# alphanewt_v0_5.net
KiCad netlist of a schematic drawn in EAGLE
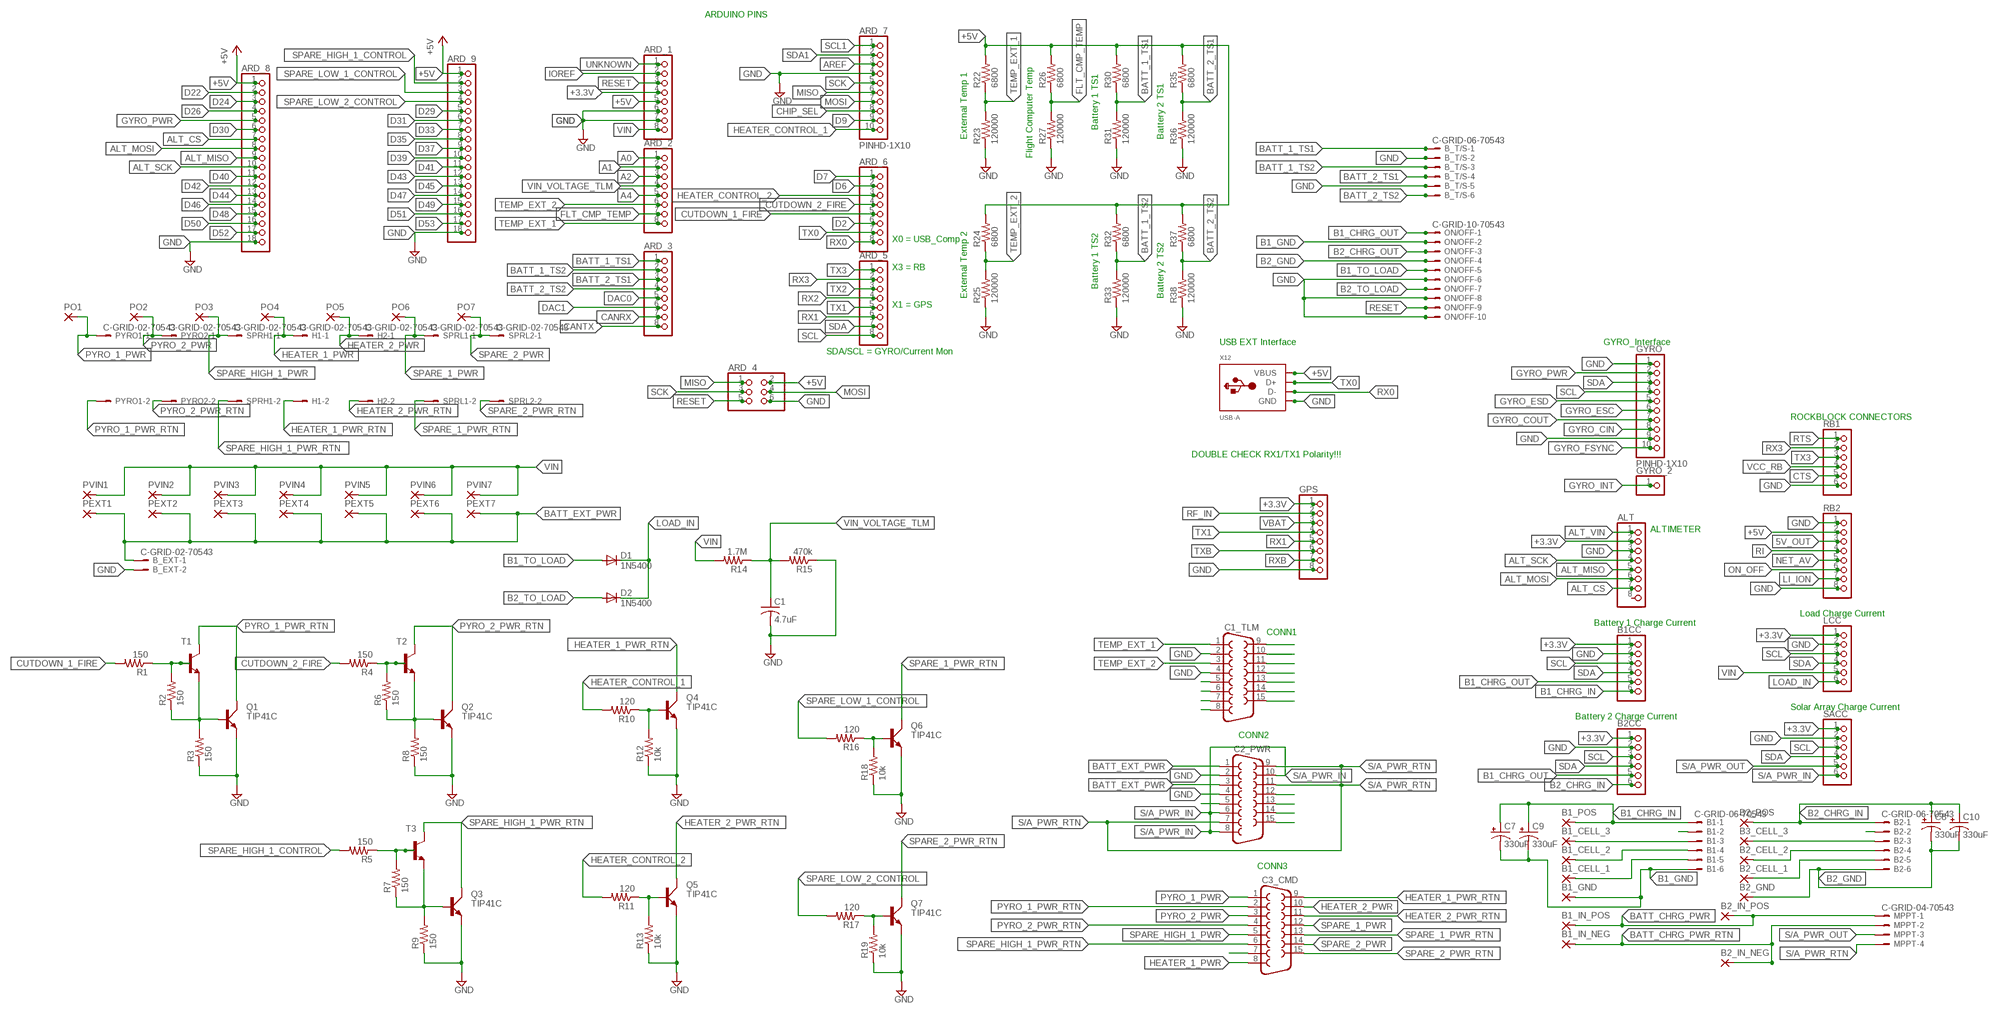
[diagram p0: schematic, sheet 1]

(export (version "E")
  (design (tool "Eeschema 10.0.6"))
  (components
    (comp (ref "ALT")
      (value "PINHD-1X8BIG")
      (footprint "eagle-import:1X08-BIG")
      (libsource (lib "eagle-import") (part "PINHD-1X8BIG"))
    )
    (comp (ref "ARD_1")
      (value "PINHD-1X8BIG")
      (footprint "eagle-import:1X08-BIG")
      (libsource (lib "eagle-import") (part "PINHD-1X8BIG"))
    )
    (comp (ref "ARD_2")
      (value "PINHD-1X8BIG")
      (footprint "eagle-import:1X08-BIG")
      (libsource (lib "eagle-import") (part "PINHD-1X8BIG"))
    )
    (comp (ref "ARD_3")
      (value "PINHD-1X8BIG")
      (footprint "eagle-import:1X08-BIG")
      (libsource (lib "eagle-import") (part "PINHD-1X8BIG"))
    )
    (comp (ref "ARD_4")
      (value "PINHD-2X3")
      (footprint "eagle-import:2X03")
      (libsource (lib "eagle-import") (part "PINHD-2X3"))
    )
    (comp (ref "ARD_5")
      (value "PINHD-1X8BIG")
      (footprint "eagle-import:1X08-BIG")
      (libsource (lib "eagle-import") (part "PINHD-1X8BIG"))
    )
    (comp (ref "ARD_6")
      (value "PINHD-1X8BIG")
      (footprint "eagle-import:1X08-BIG")
      (libsource (lib "eagle-import") (part "PINHD-1X8BIG"))
    )
    (comp (ref "ARD_7")
      (value "PINHD-1X10")
      (footprint "eagle-import:1X10-BIG")
      (libsource (lib "eagle-import") (part "PINHD-1X10"))
    )
    (comp (ref "ARD_8")
      (value "PINHD-1X18-BIG")
      (footprint "eagle-import:1X18-BIG")
      (libsource (lib "eagle-import") (part "PINHD-1X18-BIG"))
    )
    (comp (ref "ARD_9")
      (value "PINHD-1X18-BIG")
      (footprint "eagle-import:1X18-BIG")
      (libsource (lib "eagle-import") (part "PINHD-1X18-BIG"))
    )
    (comp (ref "B1")
      (value "C-GRID-06-70543")
      (footprint "eagle-import:70543-06")
      (fields
        (field (name "MF") "MOLEX")
        (field (name "MPN") "70543-0005")
        (field (name "OC_NEWARK") "59H2647")
      )
      (libsource (lib "eagle-import") (part "C-GRID-06-70543"))
    )
    (comp (ref "B1CC")
      (value "PINHD-1X6B")
      (footprint "eagle-import:1X06-BIG")
      (libsource (lib "eagle-import") (part "PINHD-1X6B"))
    )
    (comp (ref "B1_CELL_1")
      (value "SMD5")
      (footprint "eagle-import:SMD2,54-5,08")
      (libsource (lib "eagle-import") (part "SMD5"))
    )
    (comp (ref "B1_CELL_2")
      (value "SMD5")
      (footprint "eagle-import:SMD2,54-5,08")
      (libsource (lib "eagle-import") (part "SMD5"))
    )
    (comp (ref "B1_CELL_3")
      (value "SMD5")
      (footprint "eagle-import:SMD2,54-5,08")
      (libsource (lib "eagle-import") (part "SMD5"))
    )
    (comp (ref "B1_GND")
      (value "SMD5")
      (footprint "eagle-import:SMD2,54-5,08")
      (libsource (lib "eagle-import") (part "SMD5"))
    )
    (comp (ref "B1_IN_NEG")
      (value "SMD5")
      (footprint "eagle-import:SMD2,54-5,08")
      (libsource (lib "eagle-import") (part "SMD5"))
    )
    (comp (ref "B1_IN_POS")
      (value "SMD5")
      (footprint "eagle-import:SMD2,54-5,08")
      (libsource (lib "eagle-import") (part "SMD5"))
    )
    (comp (ref "B1_POS")
      (value "SMD5")
      (footprint "eagle-import:SMD2,54-5,08")
      (libsource (lib "eagle-import") (part "SMD5"))
    )
    (comp (ref "B2")
      (value "C-GRID-06-70543")
      (footprint "eagle-import:70543-06")
      (fields
        (field (name "MF") "MOLEX")
        (field (name "MPN") "70543-0005")
        (field (name "OC_NEWARK") "59H2647")
      )
      (libsource (lib "eagle-import") (part "C-GRID-06-70543"))
    )
    (comp (ref "B2CC")
      (value "PINHD-1X6B")
      (footprint "eagle-import:1X06-BIG")
      (libsource (lib "eagle-import") (part "PINHD-1X6B"))
    )
    (comp (ref "B2_CELL_1")
      (value "SMD5")
      (footprint "eagle-import:SMD2,54-5,08")
      (libsource (lib "eagle-import") (part "SMD5"))
    )
    (comp (ref "B2_CELL_2")
      (value "SMD5")
      (footprint "eagle-import:SMD2,54-5,08")
      (libsource (lib "eagle-import") (part "SMD5"))
    )
    (comp (ref "B2_GND")
      (value "SMD5")
      (footprint "eagle-import:SMD2,54-5,08")
      (libsource (lib "eagle-import") (part "SMD5"))
    )
    (comp (ref "B2_IN_NEG")
      (value "SMD5")
      (footprint "eagle-import:SMD2,54-5,08")
      (libsource (lib "eagle-import") (part "SMD5"))
    )
    (comp (ref "B2_IN_POS")
      (value "SMD5")
      (footprint "eagle-import:SMD2,54-5,08")
      (libsource (lib "eagle-import") (part "SMD5"))
    )
    (comp (ref "B2_POS")
      (value "SMD5")
      (footprint "eagle-import:SMD2,54-5,08")
      (libsource (lib "eagle-import") (part "SMD5"))
    )
    (comp (ref "B3_CELL_3")
      (value "SMD5")
      (footprint "eagle-import:SMD2,54-5,08")
      (libsource (lib "eagle-import") (part "SMD5"))
    )
    (comp (ref "B_EXT")
      (value "C-GRID-02-70543")
      (footprint "eagle-import:70543-02")
      (fields
        (field (name "MF") "MOLEX")
        (field (name "MPN") "70543-0001")
        (field (name "OC_NEWARK") "59H2645")
      )
      (libsource (lib "eagle-import") (part "C-GRID-02-70543"))
    )
    (comp (ref "B_T/S")
      (value "C-GRID-06-70543")
      (footprint "eagle-import:70543-06")
      (fields
        (field (name "MF") "MOLEX")
        (field (name "MPN") "70543-0005")
        (field (name "OC_NEWARK") "59H2647")
      )
      (libsource (lib "eagle-import") (part "C-GRID-06-70543"))
    )
    (comp (ref "C1")
      (value "4.7uF")
      (footprint "eagle-import:C0805K")
      (fields (field (name "MPN") "C2012X6S1H475K125AC"))
      (libsource (lib "eagle-import") (part "C-USC0805K"))
    )
    (comp (ref "C1_TLM")
      (value "F15HP")
      (footprint "eagle-import:F15HP")
      (fields (field (name "MPN") "5504F1-15S-02A-03"))
      (libsource (lib "eagle-import") (part "F15HP"))
    )
    (comp (ref "C2_PWR")
      (value "F15HP")
      (footprint "eagle-import:F15HP")
      (fields (field (name "MPN") "5504F1-15S-02A-03"))
      (libsource (lib "eagle-import") (part "F15HP"))
    )
    (comp (ref "C3_CMD")
      (value "F15HP")
      (footprint "eagle-import:F15HP")
      (fields (field (name "MPN") "5504F1-15S-02A-03"))
      (libsource (lib "eagle-import") (part "F15HP"))
    )
    (comp (ref "C7")
      (value "330uF")
      (footprint "eagle-import:CT7343")
      (fields (field (name "MPN") "TCN4337M020R0100"))
      (libsource (lib "eagle-import") (part "CPOL-USCT7343"))
    )
    (comp (ref "C8")
      (value "330uF")
      (footprint "eagle-import:CT7343")
      (fields (field (name "MPN") "TCN4337M020R0100"))
      (libsource (lib "eagle-import") (part "CPOL-USCT7343"))
    )
    (comp (ref "C9")
      (value "330uF")
      (footprint "eagle-import:CT7343")
      (fields (field (name "MPN") "TCN4337M020R0100"))
      (libsource (lib "eagle-import") (part "CPOL-USCT7343"))
    )
    (comp (ref "C10")
      (value "330uF")
      (footprint "eagle-import:CT7343")
      (fields (field (name "MPN") "TCN4337M020R0100"))
      (libsource (lib "eagle-import") (part "CPOL-USCT7343"))
    )
    (comp (ref "D1")
      (value "1N5400")
      (footprint "eagle-import:DO201-15")
      (fields (field (name "MPN") "1N5400-E3/54"))
      (libsource (lib "eagle-import") (part "1N5400"))
    )
    (comp (ref "D2")
      (value "1N5400")
      (footprint "eagle-import:DO201-15")
      (fields (field (name "MPN") "1N5400-E3/54"))
      (libsource (lib "eagle-import") (part "1N5400"))
    )
    (comp (ref "GPS")
      (value "PINHD-1X8BIG")
      (footprint "eagle-import:1X08-BIG")
      (libsource (lib "eagle-import") (part "PINHD-1X8BIG"))
    )
    (comp (ref "GYRO")
      (value "PINHD-1X10")
      (footprint "eagle-import:1X10-BIG")
      (libsource (lib "eagle-import") (part "PINHD-1X10"))
    )
    (comp (ref "GYRO_2")
      (value "PINHD-1X1")
      (footprint "eagle-import:1X01")
      (libsource (lib "eagle-import") (part "PINHD-1X1"))
    )
    (comp (ref "H1")
      (value "C-GRID-02-70543")
      (footprint "eagle-import:70543-02")
      (fields
        (field (name "MF") "MOLEX")
        (field (name "MPN") "70543-0001")
        (field (name "OC_NEWARK") "59H2645")
      )
      (libsource (lib "eagle-import") (part "C-GRID-02-70543"))
    )
    (comp (ref "H2")
      (value "C-GRID-02-70543")
      (footprint "eagle-import:70543-02")
      (fields
        (field (name "MF") "MOLEX")
        (field (name "MPN") "70543-0001")
        (field (name "OC_NEWARK") "59H2645")
      )
      (libsource (lib "eagle-import") (part "C-GRID-02-70543"))
    )
    (comp (ref "LCC")
      (value "PINHD-1X6B")
      (footprint "eagle-import:1X06-BIG")
      (libsource (lib "eagle-import") (part "PINHD-1X6B"))
    )
    (comp (ref "MPPT")
      (value "C-GRID-04-70543")
      (footprint "eagle-import:70543-04")
      (fields
        (field (name "MF") "MOLEX")
        (field (name "MPN") "70543-0038")
        (field (name "OC_NEWARK") "59H2665")
      )
      (libsource (lib "eagle-import") (part "C-GRID-04-70543"))
    )
    (comp (ref "ON/OFF")
      (value "C-GRID-10-70543")
      (footprint "eagle-import:70543-10")
      (fields
        (field (name "MF") "MOLEX")
        (field (name "MPN") "70543-0009")
        (field (name "OC_NEWARK") "59H2651")
      )
      (libsource (lib "eagle-import") (part "C-GRID-10-70543"))
    )
    (comp (ref "PEXT1")
      (value "SMD2")
      (footprint "eagle-import:SMD1,27-2,54")
      (libsource (lib "eagle-import") (part "SMD2"))
    )
    (comp (ref "PEXT2")
      (value "SMD2")
      (footprint "eagle-import:SMD1,27-2,54")
      (libsource (lib "eagle-import") (part "SMD2"))
    )
    (comp (ref "PEXT3")
      (value "SMD2")
      (footprint "eagle-import:SMD1,27-2,54")
      (libsource (lib "eagle-import") (part "SMD2"))
    )
    (comp (ref "PEXT4")
      (value "SMD2")
      (footprint "eagle-import:SMD1,27-2,54")
      (libsource (lib "eagle-import") (part "SMD2"))
    )
    (comp (ref "PEXT5")
      (value "SMD2")
      (footprint "eagle-import:SMD1,27-2,54")
      (libsource (lib "eagle-import") (part "SMD2"))
    )
    (comp (ref "PEXT6")
      (value "SMD2")
      (footprint "eagle-import:SMD1,27-2,54")
      (libsource (lib "eagle-import") (part "SMD2"))
    )
    (comp (ref "PEXT7")
      (value "SMD2")
      (footprint "eagle-import:SMD1,27-2,54")
      (libsource (lib "eagle-import") (part "SMD2"))
    )
    (comp (ref "PO1")
      (value "SMD2")
      (footprint "eagle-import:SMD1,27-2,54")
      (libsource (lib "eagle-import") (part "SMD2"))
    )
    (comp (ref "PO2")
      (value "SMD2")
      (footprint "eagle-import:SMD1,27-2,54")
      (libsource (lib "eagle-import") (part "SMD2"))
    )
    (comp (ref "PO3")
      (value "SMD2")
      (footprint "eagle-import:SMD1,27-2,54")
      (libsource (lib "eagle-import") (part "SMD2"))
    )
    (comp (ref "PO4")
      (value "SMD2")
      (footprint "eagle-import:SMD1,27-2,54")
      (libsource (lib "eagle-import") (part "SMD2"))
    )
    (comp (ref "PO5")
      (value "SMD2")
      (footprint "eagle-import:SMD1,27-2,54")
      (libsource (lib "eagle-import") (part "SMD2"))
    )
    (comp (ref "PO6")
      (value "SMD2")
      (footprint "eagle-import:SMD1,27-2,54")
      (libsource (lib "eagle-import") (part "SMD2"))
    )
    (comp (ref "PO7")
      (value "SMD2")
      (footprint "eagle-import:SMD1,27-2,54")
      (libsource (lib "eagle-import") (part "SMD2"))
    )
    (comp (ref "PVIN1")
      (value "SMD2")
      (footprint "eagle-import:SMD1,27-2,54")
      (libsource (lib "eagle-import") (part "SMD2"))
    )
    (comp (ref "PVIN2")
      (value "SMD2")
      (footprint "eagle-import:SMD1,27-2,54")
      (libsource (lib "eagle-import") (part "SMD2"))
    )
    (comp (ref "PVIN3")
      (value "SMD2")
      (footprint "eagle-import:SMD1,27-2,54")
      (libsource (lib "eagle-import") (part "SMD2"))
    )
    (comp (ref "PVIN4")
      (value "SMD2")
      (footprint "eagle-import:SMD1,27-2,54")
      (libsource (lib "eagle-import") (part "SMD2"))
    )
    (comp (ref "PVIN5")
      (value "SMD2")
      (footprint "eagle-import:SMD1,27-2,54")
      (libsource (lib "eagle-import") (part "SMD2"))
    )
    (comp (ref "PVIN6")
      (value "SMD2")
      (footprint "eagle-import:SMD1,27-2,54")
      (libsource (lib "eagle-import") (part "SMD2"))
    )
    (comp (ref "PVIN7")
      (value "SMD2")
      (footprint "eagle-import:SMD1,27-2,54")
      (libsource (lib "eagle-import") (part "SMD2"))
    )
    (comp (ref "PYRO1")
      (value "C-GRID-02-70543")
      (footprint "eagle-import:70543-02")
      (fields
        (field (name "MF") "MOLEX")
        (field (name "MPN") "70543-0001")
        (field (name "OC_NEWARK") "59H2645")
      )
      (libsource (lib "eagle-import") (part "C-GRID-02-70543"))
    )
    (comp (ref "PYRO2")
      (value "C-GRID-02-70543")
      (footprint "eagle-import:70543-02")
      (fields
        (field (name "MF") "MOLEX")
        (field (name "MPN") "70543-0001")
        (field (name "OC_NEWARK") "59H2645")
      )
      (libsource (lib "eagle-import") (part "C-GRID-02-70543"))
    )
    (comp (ref "Q1")
      (value "TIP41C")
      (footprint "eagle-import:TO220AV")
      (fields (field (name "MF") "FAIRCHILD SEMICONDUCTOR"))
      (libsource (lib "eagle-import") (part "TIP41C"))
    )
    (comp (ref "Q2")
      (value "TIP41C")
      (footprint "eagle-import:TO220AV")
      (fields (field (name "MF") "FAIRCHILD SEMICONDUCTOR"))
      (libsource (lib "eagle-import") (part "TIP41C"))
    )
    (comp (ref "Q3")
      (value "TIP41C")
      (footprint "eagle-import:TO220AV")
      (fields (field (name "MF") "FAIRCHILD SEMICONDUCTOR"))
      (libsource (lib "eagle-import") (part "TIP41C"))
    )
    (comp (ref "Q4")
      (value "TIP41C")
      (footprint "eagle-import:TO220AV")
      (fields (field (name "MF") "FAIRCHILD SEMICONDUCTOR"))
      (libsource (lib "eagle-import") (part "TIP41C"))
    )
    (comp (ref "Q5")
      (value "TIP41C")
      (footprint "eagle-import:TO220AV")
      (fields (field (name "MF") "FAIRCHILD SEMICONDUCTOR"))
      (libsource (lib "eagle-import") (part "TIP41C"))
    )
    (comp (ref "Q6")
      (value "TIP41C")
      (footprint "eagle-import:TO220AV")
      (fields (field (name "MF") "FAIRCHILD SEMICONDUCTOR"))
      (libsource (lib "eagle-import") (part "TIP41C"))
    )
    (comp (ref "Q7")
      (value "TIP41C")
      (footprint "eagle-import:TO220AV")
      (fields (field (name "MF") "FAIRCHILD SEMICONDUCTOR"))
      (libsource (lib "eagle-import") (part "TIP41C"))
    )
    (comp (ref "R1")
      (value "150")
      (footprint "eagle-import:R0805")
      (fields (field (name "MF") "VISHAY/DALE") (field (name "MPN") "CRCW120633R2FKEA"))
      (libsource (lib "eagle-import") (part "R-US_R0805"))
    )
    (comp (ref "R2")
      (value "150")
      (footprint "eagle-import:R0805")
      (fields (field (name "MF") "VISHAY/DALE") (field (name "MPN") "CRCW120633R2FKEA"))
      (libsource (lib "eagle-import") (part "R-US_R0805"))
    )
    (comp (ref "R3")
      (value "150")
      (footprint "eagle-import:R0805")
      (fields (field (name "MF") "VISHAY/DALE") (field (name "MPN") "CRCW120633R2FKEA"))
      (libsource (lib "eagle-import") (part "R-US_R0805"))
    )
    (comp (ref "R4")
      (value "150")
      (footprint "eagle-import:R0805")
      (fields (field (name "MF") "VISHAY/DALE") (field (name "MPN") "CRCW120633R2FKEA"))
      (libsource (lib "eagle-import") (part "R-US_R0805"))
    )
    (comp (ref "R5")
      (value "150")
      (footprint "eagle-import:R0805")
      (fields (field (name "MF") "VISHAY/DALE") (field (name "MPN") "CRCW120633R2FKEA"))
      (libsource (lib "eagle-import") (part "R-US_R0805"))
    )
    (comp (ref "R6")
      (value "150")
      (footprint "eagle-import:R0805")
      (fields (field (name "MF") "VISHAY/DALE") (field (name "MPN") "CRCW120633R2FKEA"))
      (libsource (lib "eagle-import") (part "R-US_R0805"))
    )
    (comp (ref "R7")
      (value "150")
      (footprint "eagle-import:R0805")
      (fields (field (name "MF") "VISHAY/DALE") (field (name "MPN") "CRCW120633R2FKEA"))
      (libsource (lib "eagle-import") (part "R-US_R0805"))
    )
    (comp (ref "R8")
      (value "150")
      (footprint "eagle-import:R0805")
      (fields (field (name "MF") "VISHAY/DALE") (field (name "MPN") "CRCW120633R2FKEA"))
      (libsource (lib "eagle-import") (part "R-US_R0805"))
    )
    (comp (ref "R9")
      (value "150")
      (footprint "eagle-import:R0805")
      (fields (field (name "MF") "VISHAY/DALE") (field (name "MPN") "CRCW120633R2FKEA"))
      (libsource (lib "eagle-import") (part "R-US_R0805"))
    )
    (comp (ref "R10")
      (value "120")
      (footprint "eagle-import:R0805")
      (fields (field (name "MF") "VISHAY/DALE") (field (name "MPN") "CRCW120633R2FKEA"))
      (libsource (lib "eagle-import") (part "R-US_R0805"))
    )
    (comp (ref "R11")
      (value "120")
      (footprint "eagle-import:R0805")
      (fields (field (name "MF") "VISHAY/DALE") (field (name "MPN") "CRCW120633R2FKEA"))
      (libsource (lib "eagle-import") (part "R-US_R0805"))
    )
    (comp (ref "R12")
      (value "10k")
      (footprint "eagle-import:R0805")
      (fields (field (name "MF") "VISHAY/DALE") (field (name "MPN") "CRCW120633R2FKEA"))
      (libsource (lib "eagle-import") (part "R-US_R0805"))
    )
    (comp (ref "R13")
      (value "10k")
      (footprint "eagle-import:R0805")
      (fields (field (name "MF") "VISHAY/DALE") (field (name "MPN") "CRCW120633R2FKEA"))
      (libsource (lib "eagle-import") (part "R-US_R0805"))
    )
    (comp (ref "R14")
      (value "1.7M")
      (footprint "eagle-import:R0805")
      (fields (field (name "MF") "VISHAY/DALE") (field (name "MPN") "CRCW120633R2FKEA"))
      (libsource (lib "eagle-import") (part "R-US_R0805"))
    )
    (comp (ref "R15")
      (value "470k")
      (footprint "eagle-import:R0805")
      (fields (field (name "MF") "VISHAY/DALE") (field (name "MPN") "CRCW120633R2FKEA"))
      (libsource (lib "eagle-import") (part "R-US_R0805"))
    )
    (comp (ref "R16")
      (value "120")
      (footprint "eagle-import:R0805")
      (fields (field (name "MF") "VISHAY/DALE") (field (name "MPN") "CRCW120633R2FKEA"))
      (libsource (lib "eagle-import") (part "R-US_R0805"))
    )
    (comp (ref "R17")
      (value "120")
      (footprint "eagle-import:R0805")
      (fields (field (name "MF") "VISHAY/DALE") (field (name "MPN") "CRCW120633R2FKEA"))
      (libsource (lib "eagle-import") (part "R-US_R0805"))
    )
    (comp (ref "R18")
      (value "10k")
      (footprint "eagle-import:R0805")
      (fields (field (name "MF") "VISHAY/DALE") (field (name "MPN") "CRCW120633R2FKEA"))
      (libsource (lib "eagle-import") (part "R-US_R0805"))
    )
    (comp (ref "R19")
      (value "10k")
      (footprint "eagle-import:R0805")
      (fields (field (name "MF") "VISHAY/DALE") (field (name "MPN") "CRCW120633R2FKEA"))
      (libsource (lib "eagle-import") (part "R-US_R0805"))
    )
    (comp (ref "R22")
      (value "6800")
      (footprint "eagle-import:R0805")
      (fields (field (name "MF") "VISHAY/DALE") (field (name "MPN") "CRCW120633R2FKEA"))
      (libsource (lib "eagle-import") (part "R-US_R0805"))
    )
    (comp (ref "R23")
      (value "120000")
      (footprint "eagle-import:R0805")
      (fields (field (name "MF") "VISHAY/DALE") (field (name "MPN") "CRCW120633R2FKEA"))
      (libsource (lib "eagle-import") (part "R-US_R0805"))
    )
    (comp (ref "R24")
      (value "6800")
      (footprint "eagle-import:R0805")
      (fields (field (name "MF") "VISHAY/DALE") (field (name "MPN") "CRCW120633R2FKEA"))
      (libsource (lib "eagle-import") (part "R-US_R0805"))
    )
    (comp (ref "R25")
      (value "120000")
      (footprint "eagle-import:R0805")
      (fields (field (name "MF") "VISHAY/DALE") (field (name "MPN") "CRCW120633R2FKEA"))
      (libsource (lib "eagle-import") (part "R-US_R0805"))
    )
    (comp (ref "R26")
      (value "6800")
      (footprint "eagle-import:R0805")
      (fields (field (name "MF") "VISHAY/DALE") (field (name "MPN") "CRCW120633R2FKEA"))
      (libsource (lib "eagle-import") (part "R-US_R0805"))
    )
    (comp (ref "R27")
      (value "120000")
      (footprint "eagle-import:R0805")
      (fields (field (name "MF") "VISHAY/DALE") (field (name "MPN") "CRCW120633R2FKEA"))
      (libsource (lib "eagle-import") (part "R-US_R0805"))
    )
    (comp (ref "R30")
      (value "6800")
      (footprint "eagle-import:R0805")
      (fields (field (name "MF") "VISHAY/DALE") (field (name "MPN") "CRCW120633R2FKEA"))
      (libsource (lib "eagle-import") (part "R-US_R0805"))
    )
    (comp (ref "R31")
      (value "120000")
      (footprint "eagle-import:R0805")
      (fields (field (name "MF") "VISHAY/DALE") (field (name "MPN") "CRCW120633R2FKEA"))
      (libsource (lib "eagle-import") (part "R-US_R0805"))
    )
    (comp (ref "R32")
      (value "6800")
      (footprint "eagle-import:R0805")
      (fields (field (name "MF") "VISHAY/DALE") (field (name "MPN") "CRCW120633R2FKEA"))
      (libsource (lib "eagle-import") (part "R-US_R0805"))
    )
    (comp (ref "R33")
      (value "120000")
      (footprint "eagle-import:R0805")
      (fields (field (name "MF") "VISHAY/DALE") (field (name "MPN") "CRCW120633R2FKEA"))
      (libsource (lib "eagle-import") (part "R-US_R0805"))
    )
    (comp (ref "R35")
      (value "6800")
      (footprint "eagle-import:R0805")
      (fields (field (name "MF") "VISHAY/DALE") (field (name "MPN") "CRCW120633R2FKEA"))
      (libsource (lib "eagle-import") (part "R-US_R0805"))
    )
    (comp (ref "R36")
      (value "120000")
      (footprint "eagle-import:R0805")
      (fields (field (name "MF") "VISHAY/DALE") (field (name "MPN") "CRCW120633R2FKEA"))
      (libsource (lib "eagle-import") (part "R-US_R0805"))
    )
    (comp (ref "R37")
      (value "6800")
      (footprint "eagle-import:R0805")
      (fields (field (name "MF") "VISHAY/DALE") (field (name "MPN") "CRCW120633R2FKEA"))
      (libsource (lib "eagle-import") (part "R-US_R0805"))
    )
    (comp (ref "R38")
      (value "120000")
      (footprint "eagle-import:R0805")
      (fields (field (name "MF") "VISHAY/DALE") (field (name "MPN") "CRCW120633R2FKEA"))
      (libsource (lib "eagle-import") (part "R-US_R0805"))
    )
    (comp (ref "RB1")
      (value "PINHD-1X6CB")
      (footprint "eagle-import:1X06-CLEANBIG")
      (libsource (lib "eagle-import") (part "PINHD-1X6CB"))
    )
    (comp (ref "RB2")
      (value "PINHD-1X8BIG")
      (footprint "eagle-import:1X08-BIG")
      (libsource (lib "eagle-import") (part "PINHD-1X8BIG"))
    )
    (comp (ref "SACC")
      (value "PINHD-1X6B")
      (footprint "eagle-import:1X06-BIG")
      (libsource (lib "eagle-import") (part "PINHD-1X6B"))
    )
    (comp (ref "SPRH1")
      (value "C-GRID-02-70543")
      (footprint "eagle-import:70543-02")
      (fields
        (field (name "MF") "MOLEX")
        (field (name "MPN") "70543-0001")
        (field (name "OC_NEWARK") "59H2645")
      )
      (libsource (lib "eagle-import") (part "C-GRID-02-70543"))
    )
    (comp (ref "SPRL1")
      (value "C-GRID-02-70543")
      (footprint "eagle-import:70543-02")
      (fields
        (field (name "MF") "MOLEX")
        (field (name "MPN") "70543-0001")
        (field (name "OC_NEWARK") "59H2645")
      )
      (libsource (lib "eagle-import") (part "C-GRID-02-70543"))
    )
    (comp (ref "SPRL2")
      (value "C-GRID-02-70543")
      (footprint "eagle-import:70543-02")
      (fields
        (field (name "MF") "MOLEX")
        (field (name "MPN") "70543-0001")
        (field (name "OC_NEWARK") "59H2645")
      )
      (libsource (lib "eagle-import") (part "C-GRID-02-70543"))
    )
    (comp (ref "T1")
      (value "2N3904")
      (footprint "eagle-import:TO92")
      (fields (field (name "MF") "NTE ELECTRONICS"))
      (libsource (lib "eagle-import") (part "2N3904"))
    )
    (comp (ref "T2")
      (value "2N3904")
      (footprint "eagle-import:TO92")
      (fields (field (name "MF") "NTE ELECTRONICS"))
      (libsource (lib "eagle-import") (part "2N3904"))
    )
    (comp (ref "T3")
      (value "2N3904")
      (footprint "eagle-import:TO92")
      (fields (field (name "MF") "NTE ELECTRONICS"))
      (libsource (lib "eagle-import") (part "2N3904"))
    )
    (comp (ref "X12")
      (value "USB-A")
      (footprint "eagle-import:MOLEX_480371000")
      (fields (field (name "MPN") "UE27-AC54-10H"))
      (libsource (lib "eagle-import") (part "USB-A"))
    )
  )
  (nets
    (net (code "1") (name "+3.3V") (class "Default")
      (node (ref "ALT") (pin "2") (pinfunction "2_2") (pintype "passive"))
      (node (ref "ARD_1") (pin "4") (pinfunction "4_4") (pintype "passive"))
      (node (ref "B1CC") (pin "1") (pinfunction "1_1") (pintype "passive"))
      (node (ref "B2CC") (pin "1") (pinfunction "1_1") (pintype "passive"))
      (node (ref "GPS") (pin "1") (pinfunction "1_1") (pintype "passive"))
      (node (ref "LCC") (pin "1") (pinfunction "1_1") (pintype "passive"))
      (node (ref "SACC") (pin "1") (pinfunction "1_1") (pintype "passive"))
    )
    (net (code "2") (name "+5V") (class "Default")
      (node (ref "ARD_1") (pin "5") (pinfunction "5_5") (pintype "passive"))
      (node (ref "ARD_4") (pin "2") (pinfunction "2_2") (pintype "passive"))
      (node (ref "ARD_8") (pin "1") (pinfunction "1_1") (pintype "passive"))
      (node (ref "ARD_9") (pin "1") (pinfunction "1_1") (pintype "passive"))
      (node (ref "R22") (pin "2") (pinfunction "2_2") (pintype "passive"))
      (node (ref "R24") (pin "2") (pinfunction "2_2") (pintype "passive"))
      (node (ref "R26") (pin "2") (pinfunction "2_2") (pintype "passive"))
      (node (ref "R30") (pin "2") (pinfunction "2_2") (pintype "passive"))
      (node (ref "R32") (pin "2") (pinfunction "2_2") (pintype "passive"))
      (node (ref "R35") (pin "2") (pinfunction "2_2") (pintype "passive"))
      (node (ref "R37") (pin "2") (pinfunction "2_2") (pintype "passive"))
      (node (ref "RB2") (pin "2") (pinfunction "2_2") (pintype "passive"))
      (node (ref "X12") (pin "1") (pinfunction "VBUS_1") (pintype "power_in"))
    )
    (net (code "3") (name "5V_OUT") (class "Default")
      (node (ref "RB2") (pin "3") (pinfunction "3_3") (pintype "passive"))
    )
    (net (code "4") (name "A0") (class "Default")
      (node (ref "ARD_2") (pin "1") (pinfunction "1_1") (pintype "passive"))
    )
    (net (code "5") (name "A1") (class "Default")
      (node (ref "ARD_2") (pin "2") (pinfunction "2_2") (pintype "passive"))
    )
    (net (code "6") (name "A2") (class "Default")
      (node (ref "ARD_2") (pin "3") (pinfunction "3_3") (pintype "passive"))
    )
    (net (code "7") (name "A4") (class "Default")
      (node (ref "ARD_2") (pin "5") (pinfunction "5_5") (pintype "passive"))
    )
    (net (code "8") (name "ALT_CS") (class "Default")
      (node (ref "ALT") (pin "7") (pinfunction "7_7") (pintype "passive"))
      (node (ref "ARD_8") (pin "7") (pinfunction "7_7") (pintype "passive"))
    )
    (net (code "9") (name "ALT_MISO") (class "Default")
      (node (ref "ALT") (pin "5") (pinfunction "5_5") (pintype "passive"))
      (node (ref "ARD_8") (pin "9") (pinfunction "9_9") (pintype "passive"))
    )
    (net (code "10") (name "ALT_MOSI") (class "Default")
      (node (ref "ALT") (pin "6") (pinfunction "6_6") (pintype "passive"))
      (node (ref "ARD_8") (pin "8") (pinfunction "8_8") (pintype "passive"))
    )
    (net (code "11") (name "ALT_SCK") (class "Default")
      (node (ref "ALT") (pin "4") (pinfunction "4_4") (pintype "passive"))
      (node (ref "ARD_8") (pin "10") (pinfunction "10_10") (pintype "passive"))
    )
    (net (code "12") (name "ALT_VIN") (class "Default")
      (node (ref "ALT") (pin "1") (pinfunction "1_1") (pintype "passive"))
    )
    (net (code "13") (name "AREF") (class "Default")
      (node (ref "ARD_7") (pin "3") (pinfunction "3_3") (pintype "passive"))
    )
    (net (code "14") (name "B1_CHRG_IN") (class "Default")
      (node (ref "B1") (pin "1") (pinfunction "S_1") (pintype "passive"))
      (node (ref "B1CC") (pin "6") (pinfunction "6_6") (pintype "passive"))
      (node (ref "B1_POS") (pin "1") (pinfunction "P_1") (pintype "passive"))
      (node (ref "C7") (pin "+") (pinfunction "+_+") (pintype "passive"))
      (node (ref "C9") (pin "+") (pinfunction "+_+") (pintype "passive"))
    )
    (net (code "15") (name "B1_CHRG_OUT") (class "Default")
      (node (ref "B1CC") (pin "5") (pinfunction "5_5") (pintype "passive"))
      (node (ref "B2CC") (pin "5") (pinfunction "5_5") (pintype "passive"))
      (node (ref "ON/OFF") (pin "1") (pinfunction "S_1") (pintype "passive"))
    )
    (net (code "16") (name "B1_GND") (class "Default")
      (node (ref "B1") (pin "6") (pinfunction "S_6") (pintype "passive"))
      (node (ref "B1_GND") (pin "1") (pinfunction "P_1") (pintype "passive"))
      (node (ref "C7") (pin "-") (pinfunction "-_-") (pintype "passive"))
      (node (ref "C9") (pin "-") (pinfunction "-_-") (pintype "passive"))
      (node (ref "ON/OFF") (pin "2") (pinfunction "S_2") (pintype "passive"))
    )
    (net (code "17") (name "B1_TO_LOAD") (class "Default")
      (node (ref "D1") (pin "A") (pinfunction "A_A") (pintype "passive"))
      (node (ref "ON/OFF") (pin "5") (pinfunction "S_5") (pintype "passive"))
    )
    (net (code "18") (name "B2_CHRG_IN") (class "Default")
      (node (ref "B2") (pin "1") (pinfunction "S_1") (pintype "passive"))
      (node (ref "B2CC") (pin "6") (pinfunction "6_6") (pintype "passive"))
      (node (ref "B2_POS") (pin "1") (pinfunction "P_1") (pintype "passive"))
      (node (ref "C10") (pin "+") (pinfunction "+_+") (pintype "passive"))
      (node (ref "C8") (pin "+") (pinfunction "+_+") (pintype "passive"))
    )
    (net (code "19") (name "B2_CHRG_OUT") (class "Default")
      (node (ref "ON/OFF") (pin "3") (pinfunction "S_3") (pintype "passive"))
    )
    (net (code "20") (name "B2_GND") (class "Default")
      (node (ref "B2") (pin "6") (pinfunction "S_6") (pintype "passive"))
      (node (ref "B2_GND") (pin "1") (pinfunction "P_1") (pintype "passive"))
      (node (ref "C10") (pin "-") (pinfunction "-_-") (pintype "passive"))
      (node (ref "C8") (pin "-") (pinfunction "-_-") (pintype "passive"))
      (node (ref "ON/OFF") (pin "4") (pinfunction "S_4") (pintype "passive"))
    )
    (net (code "21") (name "B2_TO_LOAD") (class "Default")
      (node (ref "D2") (pin "A") (pinfunction "A_A") (pintype "passive"))
      (node (ref "ON/OFF") (pin "7") (pinfunction "S_7") (pintype "passive"))
    )
    (net (code "22") (name "BATT_1_TS1") (class "Default")
      (node (ref "ARD_3") (pin "1") (pinfunction "1_1") (pintype "passive"))
      (node (ref "B_T/S") (pin "1") (pinfunction "S_1") (pintype "passive"))
      (node (ref "R30") (pin "1") (pinfunction "1_1") (pintype "passive"))
      (node (ref "R31") (pin "2") (pinfunction "2_2") (pintype "passive"))
    )
    (net (code "23") (name "BATT_1_TS2") (class "Default")
      (node (ref "ARD_3") (pin "2") (pinfunction "2_2") (pintype "passive"))
      (node (ref "B_T/S") (pin "3") (pinfunction "S_3") (pintype "passive"))
      (node (ref "R32") (pin "1") (pinfunction "1_1") (pintype "passive"))
      (node (ref "R33") (pin "2") (pinfunction "2_2") (pintype "passive"))
    )
    (net (code "24") (name "BATT_2_TS1") (class "Default")
      (node (ref "ARD_3") (pin "3") (pinfunction "3_3") (pintype "passive"))
      (node (ref "B_T/S") (pin "4") (pinfunction "S_4") (pintype "passive"))
      (node (ref "R35") (pin "1") (pinfunction "1_1") (pintype "passive"))
      (node (ref "R36") (pin "2") (pinfunction "2_2") (pintype "passive"))
    )
    (net (code "25") (name "BATT_2_TS2") (class "Default")
      (node (ref "ARD_3") (pin "4") (pinfunction "4_4") (pintype "passive"))
      (node (ref "B_T/S") (pin "6") (pinfunction "S_6") (pintype "passive"))
      (node (ref "R37") (pin "1") (pinfunction "1_1") (pintype "passive"))
      (node (ref "R38") (pin "2") (pinfunction "2_2") (pintype "passive"))
    )
    (net (code "26") (name "BATT_CHRG_PWR") (class "Default")
      (node (ref "B1_IN_POS") (pin "1") (pinfunction "P_1") (pintype "passive"))
      (node (ref "B2_IN_POS") (pin "1") (pinfunction "P_1") (pintype "passive"))
      (node (ref "MPPT") (pin "1") (pinfunction "S_1") (pintype "passive"))
    )
    (net (code "27") (name "BATT_CHRG_PWR_RTN") (class "Default")
      (node (ref "B1_IN_NEG") (pin "1") (pinfunction "P_1") (pintype "passive"))
      (node (ref "B2_IN_NEG") (pin "1") (pinfunction "P_1") (pintype "passive"))
      (node (ref "MPPT") (pin "2") (pinfunction "S_2") (pintype "passive"))
    )
    (net (code "28") (name "BATT_EXT_PWR") (class "Default")
      (node (ref "B_EXT") (pin "1") (pinfunction "S_1") (pintype "passive"))
      (node (ref "C2_PWR") (pin "1") (pinfunction "1_1") (pintype "passive"))
      (node (ref "C2_PWR") (pin "3") (pinfunction "3_3") (pintype "passive"))
      (node (ref "PEXT1") (pin "1") (pinfunction "P_1") (pintype "passive"))
      (node (ref "PEXT2") (pin "1") (pinfunction "P_1") (pintype "passive"))
      (node (ref "PEXT3") (pin "1") (pinfunction "P_1") (pintype "passive"))
      (node (ref "PEXT4") (pin "1") (pinfunction "P_1") (pintype "passive"))
      (node (ref "PEXT5") (pin "1") (pinfunction "P_1") (pintype "passive"))
      (node (ref "PEXT6") (pin "1") (pinfunction "P_1") (pintype "passive"))
      (node (ref "PEXT7") (pin "1") (pinfunction "P_1") (pintype "passive"))
    )
    (net (code "29") (name "CANRX") (class "Default")
      (node (ref "ARD_3") (pin "7") (pinfunction "7_7") (pintype "passive"))
    )
    (net (code "30") (name "CANTX") (class "Default")
      (node (ref "ARD_3") (pin "8") (pinfunction "8_8") (pintype "passive"))
    )
    (net (code "31") (name "CHIP_SEL") (class "Default")
      (node (ref "ARD_7") (pin "8") (pinfunction "8_8") (pintype "passive"))
    )
    (net (code "32") (name "CTS") (class "Default")
      (node (ref "RB1") (pin "5") (pinfunction "5_5") (pintype "passive"))
    )
    (net (code "33") (name "CUTDOWN_1_FIRE") (class "Default")
      (node (ref "ARD_6") (pin "5") (pinfunction "5_5") (pintype "passive"))
      (node (ref "R1") (pin "2") (pinfunction "2_2") (pintype "passive"))
    )
    (net (code "34") (name "CUTDOWN_2_FIRE") (class "Default")
      (node (ref "ARD_6") (pin "4") (pinfunction "4_4") (pintype "passive"))
      (node (ref "R4") (pin "2") (pinfunction "2_2") (pintype "passive"))
    )
    (net (code "35") (name "D2") (class "Default")
      (node (ref "ARD_6") (pin "6") (pinfunction "6_6") (pintype "passive"))
    )
    (net (code "36") (name "D6") (class "Default")
      (node (ref "ARD_6") (pin "2") (pinfunction "2_2") (pintype "passive"))
    )
    (net (code "37") (name "D7") (class "Default")
      (node (ref "ARD_6") (pin "1") (pinfunction "1_1") (pintype "passive"))
    )
    (net (code "38") (name "D9") (class "Default")
      (node (ref "ARD_7") (pin "9") (pinfunction "9_9") (pintype "passive"))
    )
    (net (code "39") (name "D22") (class "Default")
      (node (ref "ARD_8") (pin "2") (pinfunction "2_2") (pintype "passive"))
    )
    (net (code "40") (name "D24") (class "Default")
      (node (ref "ARD_8") (pin "3") (pinfunction "3_3") (pintype "passive"))
    )
    (net (code "41") (name "D26") (class "Default")
      (node (ref "ARD_8") (pin "4") (pinfunction "4_4") (pintype "passive"))
    )
    (net (code "42") (name "D29") (class "Default")
      (node (ref "ARD_9") (pin "5") (pinfunction "5_5") (pintype "passive"))
    )
    (net (code "43") (name "D30") (class "Default")
      (node (ref "ARD_8") (pin "6") (pinfunction "6_6") (pintype "passive"))
    )
    (net (code "44") (name "D31") (class "Default")
      (node (ref "ARD_9") (pin "6") (pinfunction "6_6") (pintype "passive"))
    )
    (net (code "45") (name "D33") (class "Default")
      (node (ref "ARD_9") (pin "7") (pinfunction "7_7") (pintype "passive"))
    )
    (net (code "46") (name "D35") (class "Default")
      (node (ref "ARD_9") (pin "8") (pinfunction "8_8") (pintype "passive"))
    )
    (net (code "47") (name "D37") (class "Default")
      (node (ref "ARD_9") (pin "9") (pinfunction "9_9") (pintype "passive"))
    )
    (net (code "48") (name "D39") (class "Default")
      (node (ref "ARD_9") (pin "10") (pinfunction "10_10") (pintype "passive"))
    )
    (net (code "49") (name "D40") (class "Default")
      (node (ref "ARD_8") (pin "11") (pinfunction "11_11") (pintype "passive"))
    )
    (net (code "50") (name "D41") (class "Default")
      (node (ref "ARD_9") (pin "11") (pinfunction "11_11") (pintype "passive"))
    )
    (net (code "51") (name "D42") (class "Default")
      (node (ref "ARD_8") (pin "12") (pinfunction "12_12") (pintype "passive"))
    )
    (net (code "52") (name "D43") (class "Default")
      (node (ref "ARD_9") (pin "12") (pinfunction "12_12") (pintype "passive"))
    )
    (net (code "53") (name "D44") (class "Default")
      (node (ref "ARD_8") (pin "13") (pinfunction "13_13") (pintype "passive"))
    )
    (net (code "54") (name "D45") (class "Default")
      (node (ref "ARD_9") (pin "13") (pinfunction "13_13") (pintype "passive"))
    )
    (net (code "55") (name "D46") (class "Default")
      (node (ref "ARD_8") (pin "14") (pinfunction "14_14") (pintype "passive"))
    )
    (net (code "56") (name "D47") (class "Default")
      (node (ref "ARD_9") (pin "14") (pinfunction "14_14") (pintype "passive"))
    )
    (net (code "57") (name "D48") (class "Default")
      (node (ref "ARD_8") (pin "15") (pinfunction "15_15") (pintype "passive"))
    )
    (net (code "58") (name "D49") (class "Default")
      (node (ref "ARD_9") (pin "15") (pinfunction "15_15") (pintype "passive"))
    )
    (net (code "59") (name "D50") (class "Default")
      (node (ref "ARD_8") (pin "16") (pinfunction "16_16") (pintype "passive"))
    )
    (net (code "60") (name "D51") (class "Default")
      (node (ref "ARD_9") (pin "16") (pinfunction "16_16") (pintype "passive"))
    )
    (net (code "61") (name "D52") (class "Default")
      (node (ref "ARD_8") (pin "17") (pinfunction "17_17") (pintype "passive"))
    )
    (net (code "62") (name "D53") (class "Default")
      (node (ref "ARD_9") (pin "17") (pinfunction "17_17") (pintype "passive"))
    )
    (net (code "63") (name "DAC0") (class "Default")
      (node (ref "ARD_3") (pin "5") (pinfunction "5_5") (pintype "passive"))
    )
    (net (code "64") (name "DAC1") (class "Default")
      (node (ref "ARD_3") (pin "6") (pinfunction "6_6") (pintype "passive"))
    )
    (net (code "65") (name "FLT_CMP_TEMP") (class "Default")
      (node (ref "ARD_2") (pin "7") (pinfunction "7_7") (pintype "passive"))
      (node (ref "R26") (pin "1") (pinfunction "1_1") (pintype "passive"))
      (node (ref "R27") (pin "2") (pinfunction "2_2") (pintype "passive"))
    )
    (net (code "66") (name "GND") (class "Default")
      (node (ref "ALT") (pin "3") (pinfunction "3_3") (pintype "passive"))
      (node (ref "ARD_1") (pin "6") (pinfunction "6_6") (pintype "passive"))
      (node (ref "ARD_1") (pin "7") (pinfunction "7_7") (pintype "passive"))
      (node (ref "ARD_4") (pin "6") (pinfunction "6_6") (pintype "passive"))
      (node (ref "ARD_7") (pin "4") (pinfunction "4_4") (pintype "passive"))
      (node (ref "ARD_8") (pin "18") (pinfunction "18_18") (pintype "passive"))
      (node (ref "ARD_9") (pin "18") (pinfunction "18_18") (pintype "passive"))
      (node (ref "B1CC") (pin "2") (pinfunction "2_2") (pintype "passive"))
      (node (ref "B2CC") (pin "2") (pinfunction "2_2") (pintype "passive"))
      (node (ref "B_EXT") (pin "2") (pinfunction "S_2") (pintype "passive"))
      (node (ref "B_T/S") (pin "2") (pinfunction "S_2") (pintype "passive"))
      (node (ref "B_T/S") (pin "5") (pinfunction "S_5") (pintype "passive"))
      (node (ref "C1") (pin "2") (pinfunction "2_2") (pintype "passive"))
      (node (ref "C1_TLM") (pin "2") (pinfunction "2_2") (pintype "passive"))
      (node (ref "C1_TLM") (pin "4") (pinfunction "4_4") (pintype "passive"))
      (node (ref "C2_PWR") (pin "2") (pinfunction "2_2") (pintype "passive"))
      (node (ref "C2_PWR") (pin "4") (pinfunction "4_4") (pintype "passive"))
      (node (ref "GPS") (pin "8") (pinfunction "8_8") (pintype "passive"))
      (node (ref "GYRO") (pin "1") (pinfunction "1_1") (pintype "passive"))
      (node (ref "GYRO") (pin "9") (pinfunction "9_9") (pintype "passive"))
      (node (ref "LCC") (pin "2") (pinfunction "2_2") (pintype "passive"))
      (node (ref "ON/OFF") (pin "10") (pinfunction "S_10") (pintype "passive"))
      (node (ref "ON/OFF") (pin "6") (pinfunction "S_6") (pintype "passive"))
      (node (ref "ON/OFF") (pin "8") (pinfunction "S_8") (pintype "passive"))
      (node (ref "Q1") (pin "E") (pinfunction "E_E") (pintype "passive"))
      (node (ref "Q2") (pin "E") (pinfunction "E_E") (pintype "passive"))
      (node (ref "Q3") (pin "E") (pinfunction "E_E") (pintype "passive"))
      (node (ref "Q4") (pin "E") (pinfunction "E_E") (pintype "passive"))
      (node (ref "Q5") (pin "E") (pinfunction "E_E") (pintype "passive"))
      (node (ref "Q6") (pin "E") (pinfunction "E_E") (pintype "passive"))
      (node (ref "Q7") (pin "E") (pinfunction "E_E") (pintype "passive"))
      (node (ref "R12") (pin "1") (pinfunction "1_1") (pintype "passive"))
      (node (ref "R13") (pin "1") (pinfunction "1_1") (pintype "passive"))
      (node (ref "R15") (pin "1") (pinfunction "1_1") (pintype "passive"))
      (node (ref "R18") (pin "1") (pinfunction "1_1") (pintype "passive"))
      (node (ref "R19") (pin "1") (pinfunction "1_1") (pintype "passive"))
      (node (ref "R23") (pin "1") (pinfunction "1_1") (pintype "passive"))
      (node (ref "R25") (pin "1") (pinfunction "1_1") (pintype "passive"))
      (node (ref "R27") (pin "1") (pinfunction "1_1") (pintype "passive"))
      (node (ref "R3") (pin "1") (pinfunction "1_1") (pintype "passive"))
      (node (ref "R31") (pin "1") (pinfunction "1_1") (pintype "passive"))
      (node (ref "R33") (pin "1") (pinfunction "1_1") (pintype "passive"))
      (node (ref "R36") (pin "1") (pinfunction "1_1") (pintype "passive"))
      (node (ref "R38") (pin "1") (pinfunction "1_1") (pintype "passive"))
      (node (ref "R8") (pin "1") (pinfunction "1_1") (pintype "passive"))
      (node (ref "R9") (pin "1") (pinfunction "1_1") (pintype "passive"))
      (node (ref "RB1") (pin "6") (pinfunction "6_6") (pintype "passive"))
      (node (ref "RB2") (pin "1") (pinfunction "1_1") (pintype "passive"))
      (node (ref "RB2") (pin "8") (pinfunction "8_8") (pintype "passive"))
      (node (ref "SACC") (pin "2") (pinfunction "2_2") (pintype "passive"))
      (node (ref "X12") (pin "4") (pinfunction "GND_4") (pintype "power_in"))
    )
    (net (code "67") (name "GYRO_CIN") (class "Default")
      (node (ref "GYRO") (pin "8") (pinfunction "8_8") (pintype "passive"))
    )
    (net (code "68") (name "GYRO_COUT") (class "Default")
      (node (ref "GYRO") (pin "7") (pinfunction "7_7") (pintype "passive"))
    )
    (net (code "69") (name "GYRO_ESC") (class "Default")
      (node (ref "GYRO") (pin "6") (pinfunction "6_6") (pintype "passive"))
    )
    (net (code "70") (name "GYRO_ESD") (class "Default")
      (node (ref "GYRO") (pin "5") (pinfunction "5_5") (pintype "passive"))
    )
    (net (code "71") (name "GYRO_FSYNC") (class "Default")
      (node (ref "GYRO") (pin "10") (pinfunction "10_10") (pintype "passive"))
    )
    (net (code "72") (name "GYRO_INT") (class "Default")
      (node (ref "GYRO_2") (pin "1") (pinfunction "1_1") (pintype "passive"))
    )
    (net (code "73") (name "GYRO_PWR") (class "Default")
      (node (ref "ARD_8") (pin "5") (pinfunction "5_5") (pintype "passive"))
      (node (ref "GYRO") (pin "2") (pinfunction "2_2") (pintype "passive"))
    )
    (net (code "74") (name "HEATER_1_PWR") (class "Default")
      (node (ref "C3_CMD") (pin "8") (pinfunction "8_8") (pintype "passive"))
      (node (ref "H1") (pin "1") (pinfunction "S_1") (pintype "passive"))
      (node (ref "PO4") (pin "1") (pinfunction "P_1") (pintype "passive"))
    )
    (net (code "75") (name "HEATER_1_PWR_RTN") (class "Default")
      (node (ref "C3_CMD") (pin "9") (pinfunction "9_9") (pintype "passive"))
      (node (ref "H1") (pin "2") (pinfunction "S_2") (pintype "passive"))
      (node (ref "Q4") (pin "C") (pinfunction "C_C") (pintype "passive"))
    )
    (net (code "76") (name "HEATER_2_PWR") (class "Default")
      (node (ref "C3_CMD") (pin "10") (pinfunction "10_10") (pintype "passive"))
      (node (ref "H2") (pin "1") (pinfunction "S_1") (pintype "passive"))
      (node (ref "PO5") (pin "1") (pinfunction "P_1") (pintype "passive"))
    )
    (net (code "77") (name "HEATER_2_PWR_RTN") (class "Default")
      (node (ref "C3_CMD") (pin "11") (pinfunction "11_11") (pintype "passive"))
      (node (ref "H2") (pin "2") (pinfunction "S_2") (pintype "passive"))
      (node (ref "Q5") (pin "C") (pinfunction "C_C") (pintype "passive"))
    )
    (net (code "78") (name "HEATER_CONTROL_1") (class "Default")
      (node (ref "ARD_7") (pin "10") (pinfunction "10_10") (pintype "passive"))
      (node (ref "R10") (pin "2") (pinfunction "2_2") (pintype "passive"))
    )
    (net (code "79") (name "HEATER_CONTROL_2") (class "Default")
      (node (ref "ARD_6") (pin "3") (pinfunction "3_3") (pintype "passive"))
      (node (ref "R11") (pin "2") (pinfunction "2_2") (pintype "passive"))
    )
    (net (code "80") (name "IOREF") (class "Default")
      (node (ref "ARD_1") (pin "2") (pinfunction "2_2") (pintype "passive"))
    )
    (net (code "81") (name "LI_ION") (class "Default")
      (node (ref "RB2") (pin "7") (pinfunction "7_7") (pintype "passive"))
    )
    (net (code "82") (name "LOAD_IN") (class "Default")
      (node (ref "D1") (pin "C") (pinfunction "C_C") (pintype "passive"))
      (node (ref "D2") (pin "C") (pinfunction "C_C") (pintype "passive"))
      (node (ref "LCC") (pin "6") (pinfunction "6_6") (pintype "passive"))
    )
    (net (code "83") (name "MISO") (class "Default")
      (node (ref "ARD_4") (pin "1") (pinfunction "1_1") (pintype "passive"))
      (node (ref "ARD_7") (pin "6") (pinfunction "6_6") (pintype "passive"))
    )
    (net (code "84") (name "MOSI") (class "Default")
      (node (ref "ARD_4") (pin "4") (pinfunction "4_4") (pintype "passive"))
      (node (ref "ARD_7") (pin "7") (pinfunction "7_7") (pintype "passive"))
    )
    (net (code "85") (name "NET_AV") (class "Default")
      (node (ref "RB2") (pin "5") (pinfunction "5_5") (pintype "passive"))
    )
    (net (code "86") (name "Net-(B1C-S)") (class "Default")
      (node (ref "B1") (pin "3") (pinfunction "S_3") (pintype "passive"))
      (node (ref "B1_CELL_3") (pin "1") (pinfunction "P_1") (pintype "passive"))
    )
    (net (code "87") (name "Net-(B1D-S)") (class "Default")
      (node (ref "B1") (pin "4") (pinfunction "S_4") (pintype "passive"))
      (node (ref "B1_CELL_2") (pin "1") (pinfunction "P_1") (pintype "passive"))
    )
    (net (code "88") (name "Net-(B1E-S)") (class "Default")
      (node (ref "B1") (pin "5") (pinfunction "S_5") (pintype "passive"))
      (node (ref "B1_CELL_1") (pin "1") (pinfunction "P_1") (pintype "passive"))
    )
    (net (code "89") (name "Net-(B2C-S)") (class "Default")
      (node (ref "B2") (pin "3") (pinfunction "S_3") (pintype "passive"))
      (node (ref "B3_CELL_3") (pin "1") (pinfunction "P_1") (pintype "passive"))
    )
    (net (code "90") (name "Net-(B2D-S)") (class "Default")
      (node (ref "B2") (pin "4") (pinfunction "S_4") (pintype "passive"))
      (node (ref "B2_CELL_2") (pin "1") (pinfunction "P_1") (pintype "passive"))
    )
    (net (code "91") (name "Net-(B2E-S)") (class "Default")
      (node (ref "B2") (pin "5") (pinfunction "S_5") (pintype "passive"))
      (node (ref "B2_CELL_1") (pin "1") (pinfunction "P_1") (pintype "passive"))
    )
    (net (code "92") (name "Net-(Q4-PadB)") (class "Default")
      (node (ref "Q4") (pin "B") (pinfunction "B_B") (pintype "passive"))
      (node (ref "R10") (pin "1") (pinfunction "1_1") (pintype "passive"))
      (node (ref "R12") (pin "2") (pinfunction "2_2") (pintype "passive"))
    )
    (net (code "93") (name "Net-(Q5-PadB)") (class "Default")
      (node (ref "Q5") (pin "B") (pinfunction "B_B") (pintype "passive"))
      (node (ref "R11") (pin "1") (pinfunction "1_1") (pintype "passive"))
      (node (ref "R13") (pin "2") (pinfunction "2_2") (pintype "passive"))
    )
    (net (code "94") (name "Net-(Q6-PadB)") (class "Default")
      (node (ref "Q6") (pin "B") (pinfunction "B_B") (pintype "passive"))
      (node (ref "R16") (pin "1") (pinfunction "1_1") (pintype "passive"))
      (node (ref "R18") (pin "2") (pinfunction "2_2") (pintype "passive"))
    )
    (net (code "95") (name "Net-(Q7-PadB)") (class "Default")
      (node (ref "Q7") (pin "B") (pinfunction "B_B") (pintype "passive"))
      (node (ref "R17") (pin "1") (pinfunction "1_1") (pintype "passive"))
      (node (ref "R19") (pin "2") (pinfunction "2_2") (pintype "passive"))
    )
    (net (code "96") (name "Net-(T1-B)") (class "Default")
      (node (ref "R1") (pin "1") (pinfunction "1_1") (pintype "passive"))
      (node (ref "R2") (pin "2") (pinfunction "2_2") (pintype "passive"))
      (node (ref "T1") (pin "2") (pinfunction "B_2") (pintype "passive"))
    )
    (net (code "97") (name "Net-(T1-E)") (class "Default")
      (node (ref "Q1") (pin "B") (pinfunction "B_B") (pintype "passive"))
      (node (ref "R2") (pin "1") (pinfunction "1_1") (pintype "passive"))
      (node (ref "R3") (pin "2") (pinfunction "2_2") (pintype "passive"))
      (node (ref "T1") (pin "3") (pinfunction "E_3") (pintype "passive"))
    )
    (net (code "98") (name "Net-(T2-B)") (class "Default")
      (node (ref "R4") (pin "1") (pinfunction "1_1") (pintype "passive"))
      (node (ref "R6") (pin "2") (pinfunction "2_2") (pintype "passive"))
      (node (ref "T2") (pin "2") (pinfunction "B_2") (pintype "passive"))
    )
    (net (code "99") (name "Net-(T2-E)") (class "Default")
      (node (ref "Q2") (pin "B") (pinfunction "B_B") (pintype "passive"))
      (node (ref "R6") (pin "1") (pinfunction "1_1") (pintype "passive"))
      (node (ref "R8") (pin "2") (pinfunction "2_2") (pintype "passive"))
      (node (ref "T2") (pin "3") (pinfunction "E_3") (pintype "passive"))
    )
    (net (code "100") (name "Net-(T3-B)") (class "Default")
      (node (ref "R5") (pin "1") (pinfunction "1_1") (pintype "passive"))
      (node (ref "R7") (pin "2") (pinfunction "2_2") (pintype "passive"))
      (node (ref "T3") (pin "2") (pinfunction "B_2") (pintype "passive"))
    )
    (net (code "101") (name "Net-(T3-E)") (class "Default")
      (node (ref "Q3") (pin "B") (pinfunction "B_B") (pintype "passive"))
      (node (ref "R7") (pin "1") (pinfunction "1_1") (pintype "passive"))
      (node (ref "R9") (pin "2") (pinfunction "2_2") (pintype "passive"))
      (node (ref "T3") (pin "3") (pinfunction "E_3") (pintype "passive"))
    )
    (net (code "102") (name "ON_OFF") (class "Default")
      (node (ref "RB2") (pin "6") (pinfunction "6_6") (pintype "passive"))
    )
    (net (code "103") (name "PYRO_1_PWR") (class "Default")
      (node (ref "C3_CMD") (pin "1") (pinfunction "1_1") (pintype "passive"))
      (node (ref "PO1") (pin "1") (pinfunction "P_1") (pintype "passive"))
      (node (ref "PYRO1") (pin "1") (pinfunction "S_1") (pintype "passive"))
    )
    (net (code "104") (name "PYRO_1_PWR_RTN") (class "Default")
      (node (ref "C3_CMD") (pin "2") (pinfunction "2_2") (pintype "passive"))
      (node (ref "PYRO1") (pin "2") (pinfunction "S_2") (pintype "passive"))
      (node (ref "Q1") (pin "C") (pinfunction "C_C") (pintype "passive"))
      (node (ref "T1") (pin "1") (pinfunction "C_1") (pintype "passive"))
    )
    (net (code "105") (name "PYRO_2_PWR") (class "Default")
      (node (ref "C3_CMD") (pin "3") (pinfunction "3_3") (pintype "passive"))
      (node (ref "PO2") (pin "1") (pinfunction "P_1") (pintype "passive"))
      (node (ref "PYRO2") (pin "1") (pinfunction "S_1") (pintype "passive"))
    )
    (net (code "106") (name "PYRO_2_PWR_RTN") (class "Default")
      (node (ref "C3_CMD") (pin "4") (pinfunction "4_4") (pintype "passive"))
      (node (ref "PYRO2") (pin "2") (pinfunction "S_2") (pintype "passive"))
      (node (ref "Q2") (pin "C") (pinfunction "C_C") (pintype "passive"))
      (node (ref "T2") (pin "1") (pinfunction "C_1") (pintype "passive"))
    )
    (net (code "107") (name "RESET") (class "Default")
      (node (ref "ARD_1") (pin "3") (pinfunction "3_3") (pintype "passive"))
      (node (ref "ARD_4") (pin "5") (pinfunction "5_5") (pintype "passive"))
      (node (ref "ON/OFF") (pin "9") (pinfunction "S_9") (pintype "passive"))
    )
    (net (code "108") (name "RF_IN") (class "Default")
      (node (ref "GPS") (pin "2") (pinfunction "2_2") (pintype "passive"))
    )
    (net (code "109") (name "RI") (class "Default")
      (node (ref "RB2") (pin "4") (pinfunction "4_4") (pintype "passive"))
    )
    (net (code "110") (name "RTS") (class "Default")
      (node (ref "RB1") (pin "1") (pinfunction "1_1") (pintype "passive"))
    )
    (net (code "111") (name "RX0") (class "Default")
      (node (ref "ARD_6") (pin "8") (pinfunction "8_8") (pintype "passive"))
      (node (ref "X12") (pin "2") (pinfunction "D-_2") (pintype "bidirectional"))
    )
    (net (code "112") (name "RX1") (class "Default")
      (node (ref "ARD_5") (pin "6") (pinfunction "6_6") (pintype "passive"))
      (node (ref "GPS") (pin "5") (pinfunction "5_5") (pintype "passive"))
    )
    (net (code "113") (name "RX2") (class "Default")
      (node (ref "ARD_5") (pin "4") (pinfunction "4_4") (pintype "passive"))
    )
    (net (code "114") (name "RX3") (class "Default")
      (node (ref "ARD_5") (pin "2") (pinfunction "2_2") (pintype "passive"))
      (node (ref "RB1") (pin "2") (pinfunction "2_2") (pintype "passive"))
    )
    (net (code "115") (name "RXB") (class "Default")
      (node (ref "GPS") (pin "7") (pinfunction "7_7") (pintype "passive"))
    )
    (net (code "116") (name "SCK") (class "Default")
      (node (ref "ARD_4") (pin "3") (pinfunction "3_3") (pintype "passive"))
      (node (ref "ARD_7") (pin "5") (pinfunction "5_5") (pintype "passive"))
    )
    (net (code "117") (name "SCL") (class "Default")
      (node (ref "ARD_5") (pin "8") (pinfunction "8_8") (pintype "passive"))
      (node (ref "B1CC") (pin "3") (pinfunction "3_3") (pintype "passive"))
      (node (ref "B2CC") (pin "3") (pinfunction "3_3") (pintype "passive"))
      (node (ref "GYRO") (pin "4") (pinfunction "4_4") (pintype "passive"))
      (node (ref "LCC") (pin "3") (pinfunction "3_3") (pintype "passive"))
      (node (ref "SACC") (pin "3") (pinfunction "3_3") (pintype "passive"))
    )
    (net (code "118") (name "SCL1") (class "Default")
      (node (ref "ARD_7") (pin "1") (pinfunction "1_1") (pintype "passive"))
    )
    (net (code "119") (name "SDA") (class "Default")
      (node (ref "ARD_5") (pin "7") (pinfunction "7_7") (pintype "passive"))
      (node (ref "B1CC") (pin "4") (pinfunction "4_4") (pintype "passive"))
      (node (ref "B2CC") (pin "4") (pinfunction "4_4") (pintype "passive"))
      (node (ref "GYRO") (pin "3") (pinfunction "3_3") (pintype "passive"))
      (node (ref "LCC") (pin "4") (pinfunction "4_4") (pintype "passive"))
      (node (ref "SACC") (pin "4") (pinfunction "4_4") (pintype "passive"))
    )
    (net (code "120") (name "SDA1") (class "Default")
      (node (ref "ARD_7") (pin "2") (pinfunction "2_2") (pintype "passive"))
    )
    (net (code "121") (name "SPARE_1_PWR") (class "Default")
      (node (ref "C3_CMD") (pin "12") (pinfunction "12_12") (pintype "passive"))
      (node (ref "PO6") (pin "1") (pinfunction "P_1") (pintype "passive"))
      (node (ref "SPRL1") (pin "1") (pinfunction "S_1") (pintype "passive"))
    )
    (net (code "122") (name "SPARE_1_PWR_RTN") (class "Default")
      (node (ref "C3_CMD") (pin "13") (pinfunction "13_13") (pintype "passive"))
      (node (ref "Q6") (pin "C") (pinfunction "C_C") (pintype "passive"))
      (node (ref "SPRL1") (pin "2") (pinfunction "S_2") (pintype "passive"))
    )
    (net (code "123") (name "SPARE_2_PWR") (class "Default")
      (node (ref "C3_CMD") (pin "14") (pinfunction "14_14") (pintype "passive"))
      (node (ref "PO7") (pin "1") (pinfunction "P_1") (pintype "passive"))
      (node (ref "SPRL2") (pin "1") (pinfunction "S_1") (pintype "passive"))
    )
    (net (code "124") (name "SPARE_2_PWR_RTN") (class "Default")
      (node (ref "C3_CMD") (pin "15") (pinfunction "15_15") (pintype "passive"))
      (node (ref "Q7") (pin "C") (pinfunction "C_C") (pintype "passive"))
      (node (ref "SPRL2") (pin "2") (pinfunction "S_2") (pintype "passive"))
    )
    (net (code "125") (name "SPARE_HIGH_1_CONTROL") (class "Default")
      (node (ref "ARD_9") (pin "2") (pinfunction "2_2") (pintype "passive"))
      (node (ref "R5") (pin "2") (pinfunction "2_2") (pintype "passive"))
    )
    (net (code "126") (name "SPARE_HIGH_1_PWR") (class "Default")
      (node (ref "C3_CMD") (pin "5") (pinfunction "5_5") (pintype "passive"))
      (node (ref "PO3") (pin "1") (pinfunction "P_1") (pintype "passive"))
      (node (ref "SPRH1") (pin "1") (pinfunction "S_1") (pintype "passive"))
    )
    (net (code "127") (name "SPARE_HIGH_1_PWR_RTN") (class "Default")
      (node (ref "C3_CMD") (pin "6") (pinfunction "6_6") (pintype "passive"))
      (node (ref "Q3") (pin "C") (pinfunction "C_C") (pintype "passive"))
      (node (ref "SPRH1") (pin "2") (pinfunction "S_2") (pintype "passive"))
      (node (ref "T3") (pin "1") (pinfunction "C_1") (pintype "passive"))
    )
    (net (code "128") (name "SPARE_LOW_1_CONTROL") (class "Default")
      (node (ref "ARD_9") (pin "3") (pinfunction "3_3") (pintype "passive"))
      (node (ref "R16") (pin "2") (pinfunction "2_2") (pintype "passive"))
    )
    (net (code "129") (name "SPARE_LOW_2_CONTROL") (class "Default")
      (node (ref "ARD_9") (pin "4") (pinfunction "4_4") (pintype "passive"))
      (node (ref "R17") (pin "2") (pinfunction "2_2") (pintype "passive"))
    )
    (net (code "130") (name "S{slash}A_PWR_IN") (class "Default")
      (node (ref "C2_PWR") (pin "10") (pinfunction "10_10") (pintype "passive"))
      (node (ref "C2_PWR") (pin "6") (pinfunction "6_6") (pintype "passive"))
      (node (ref "C2_PWR") (pin "8") (pinfunction "8_8") (pintype "passive"))
      (node (ref "SACC") (pin "6") (pinfunction "6_6") (pintype "passive"))
    )
    (net (code "131") (name "S{slash}A_PWR_OUT") (class "Default")
      (node (ref "MPPT") (pin "3") (pinfunction "S_3") (pintype "passive"))
      (node (ref "SACC") (pin "5") (pinfunction "5_5") (pintype "passive"))
    )
    (net (code "132") (name "S{slash}A_PWR_RTN") (class "Default")
      (node (ref "C2_PWR") (pin "11") (pinfunction "11_11") (pintype "passive"))
      (node (ref "C2_PWR") (pin "7") (pinfunction "7_7") (pintype "passive"))
      (node (ref "C2_PWR") (pin "9") (pinfunction "9_9") (pintype "passive"))
      (node (ref "MPPT") (pin "4") (pinfunction "S_4") (pintype "passive"))
    )
    (net (code "133") (name "TEMP_EXT_1") (class "Default")
      (node (ref "ARD_2") (pin "8") (pinfunction "8_8") (pintype "passive"))
      (node (ref "C1_TLM") (pin "1") (pinfunction "1_1") (pintype "passive"))
      (node (ref "R22") (pin "1") (pinfunction "1_1") (pintype "passive"))
      (node (ref "R23") (pin "2") (pinfunction "2_2") (pintype "passive"))
    )
    (net (code "134") (name "TEMP_EXT_2") (class "Default")
      (node (ref "ARD_2") (pin "6") (pinfunction "6_6") (pintype "passive"))
      (node (ref "C1_TLM") (pin "3") (pinfunction "3_3") (pintype "passive"))
      (node (ref "R24") (pin "1") (pinfunction "1_1") (pintype "passive"))
      (node (ref "R25") (pin "2") (pinfunction "2_2") (pintype "passive"))
    )
    (net (code "135") (name "TX0") (class "Default")
      (node (ref "ARD_6") (pin "7") (pinfunction "7_7") (pintype "passive"))
      (node (ref "X12") (pin "3") (pinfunction "D+_3") (pintype "bidirectional"))
    )
    (net (code "136") (name "TX1") (class "Default")
      (node (ref "ARD_5") (pin "5") (pinfunction "5_5") (pintype "passive"))
      (node (ref "GPS") (pin "4") (pinfunction "4_4") (pintype "passive"))
    )
    (net (code "137") (name "TX2") (class "Default")
      (node (ref "ARD_5") (pin "3") (pinfunction "3_3") (pintype "passive"))
    )
    (net (code "138") (name "TX3") (class "Default")
      (node (ref "ARD_5") (pin "1") (pinfunction "1_1") (pintype "passive"))
      (node (ref "RB1") (pin "3") (pinfunction "3_3") (pintype "passive"))
    )
    (net (code "139") (name "TXB") (class "Default")
      (node (ref "GPS") (pin "6") (pinfunction "6_6") (pintype "passive"))
    )
    (net (code "140") (name "UNKNOWN") (class "Default")
      (node (ref "ARD_1") (pin "1") (pinfunction "1_1") (pintype "passive"))
    )
    (net (code "141") (name "VBAT") (class "Default")
      (node (ref "GPS") (pin "3") (pinfunction "3_3") (pintype "passive"))
    )
    (net (code "142") (name "VCC_RB") (class "Default")
      (node (ref "RB1") (pin "4") (pinfunction "4_4") (pintype "passive"))
    )
    (net (code "143") (name "VIN") (class "Default")
      (node (ref "ARD_1") (pin "8") (pinfunction "8_8") (pintype "passive"))
      (node (ref "LCC") (pin "5") (pinfunction "5_5") (pintype "passive"))
      (node (ref "PVIN1") (pin "1") (pinfunction "P_1") (pintype "passive"))
      (node (ref "PVIN2") (pin "1") (pinfunction "P_1") (pintype "passive"))
      (node (ref "PVIN3") (pin "1") (pinfunction "P_1") (pintype "passive"))
      (node (ref "PVIN4") (pin "1") (pinfunction "P_1") (pintype "passive"))
      (node (ref "PVIN5") (pin "1") (pinfunction "P_1") (pintype "passive"))
      (node (ref "PVIN6") (pin "1") (pinfunction "P_1") (pintype "passive"))
      (node (ref "PVIN7") (pin "1") (pinfunction "P_1") (pintype "passive"))
      (node (ref "R14") (pin "2") (pinfunction "2_2") (pintype "passive"))
    )
    (net (code "144") (name "VIN_VOLTAGE_TLM") (class "Default")
      (node (ref "ARD_2") (pin "4") (pinfunction "4_4") (pintype "passive"))
      (node (ref "C1") (pin "1") (pinfunction "1_1") (pintype "passive"))
      (node (ref "R14") (pin "1") (pinfunction "1_1") (pintype "passive"))
      (node (ref "R15") (pin "2") (pinfunction "2_2") (pintype "passive"))
    )
    (net (code "145") (name "unconnected-(ALT-Pad8)") (class "Default")
      (node (ref "ALT") (pin "8") (pinfunction "8_8") (pintype "passive"))
    )
    (net (code "146") (name "unconnected-(B1B-S-Pad2)") (class "Default")
      (node (ref "B1") (pin "2") (pinfunction "S_2") (pintype "passive"))
    )
    (net (code "147") (name "unconnected-(B2B-S-Pad2)") (class "Default")
      (node (ref "B2") (pin "2") (pinfunction "S_2") (pintype "passive"))
    )
    (net (code "148") (name "unconnected-(C1_TLM-Pad5)") (class "Default")
      (node (ref "C1_TLM") (pin "5") (pinfunction "5_5") (pintype "passive"))
    )
    (net (code "149") (name "unconnected-(C1_TLM-Pad6)") (class "Default")
      (node (ref "C1_TLM") (pin "6") (pinfunction "6_6") (pintype "passive"))
    )
    (net (code "150") (name "unconnected-(C1_TLM-Pad7)") (class "Default")
      (node (ref "C1_TLM") (pin "7") (pinfunction "7_7") (pintype "passive"))
    )
    (net (code "151") (name "unconnected-(C1_TLM-Pad8)") (class "Default")
      (node (ref "C1_TLM") (pin "8") (pinfunction "8_8") (pintype "passive"))
    )
    (net (code "152") (name "unconnected-(C1_TLM-Pad9)") (class "Default")
      (node (ref "C1_TLM") (pin "9") (pinfunction "9_9") (pintype "passive"))
    )
    (net (code "153") (name "unconnected-(C1_TLM-Pad10)") (class "Default")
      (node (ref "C1_TLM") (pin "10") (pinfunction "10_10") (pintype "passive"))
    )
    (net (code "154") (name "unconnected-(C1_TLM-Pad11)") (class "Default")
      (node (ref "C1_TLM") (pin "11") (pinfunction "11_11") (pintype "passive"))
    )
    (net (code "155") (name "unconnected-(C1_TLM-Pad12)") (class "Default")
      (node (ref "C1_TLM") (pin "12") (pinfunction "12_12") (pintype "passive"))
    )
    (net (code "156") (name "unconnected-(C1_TLM-Pad13)") (class "Default")
      (node (ref "C1_TLM") (pin "13") (pinfunction "13_13") (pintype "passive"))
    )
    (net (code "157") (name "unconnected-(C1_TLM-Pad14)") (class "Default")
      (node (ref "C1_TLM") (pin "14") (pinfunction "14_14") (pintype "passive"))
    )
    (net (code "158") (name "unconnected-(C1_TLM-Pad15)") (class "Default")
      (node (ref "C1_TLM") (pin "15") (pinfunction "15_15") (pintype "passive"))
    )
    (net (code "159") (name "unconnected-(C2_PWR-Pad5)") (class "Default")
      (node (ref "C2_PWR") (pin "5") (pinfunction "5_5") (pintype "passive"))
    )
    (net (code "160") (name "unconnected-(C2_PWR-Pad12)") (class "Default")
      (node (ref "C2_PWR") (pin "12") (pinfunction "12_12") (pintype "passive"))
    )
    (net (code "161") (name "unconnected-(C2_PWR-Pad13)") (class "Default")
      (node (ref "C2_PWR") (pin "13") (pinfunction "13_13") (pintype "passive"))
    )
    (net (code "162") (name "unconnected-(C2_PWR-Pad14)") (class "Default")
      (node (ref "C2_PWR") (pin "14") (pinfunction "14_14") (pintype "passive"))
    )
    (net (code "163") (name "unconnected-(C2_PWR-Pad15)") (class "Default")
      (node (ref "C2_PWR") (pin "15") (pinfunction "15_15") (pintype "passive"))
    )
    (net (code "164") (name "unconnected-(C3_CMD-Pad7)") (class "Default")
      (node (ref "C3_CMD") (pin "7") (pinfunction "7_7") (pintype "passive"))
    )
  )
)
